# Transmitter.net
KiCad netlist of a schematic drawn in EAGLE
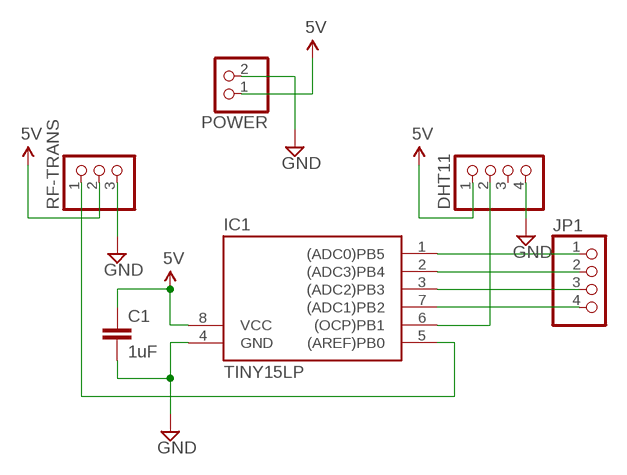
[diagram p0: schematic, sheet 1]

(export (version "E")
  (design (tool "Eeschema 10.0.6"))
  (components
    (comp (ref "C1")
      (value "1uF")
      (footprint "eagle-import:0805")
      (libsource (lib "eagle-import") (part "CAP0805"))
    )
    (comp (ref "DHT11")
      (value "PINHD-1X4")
      (footprint "eagle-import:1X04")
      (libsource (lib "eagle-import") (part "PINHD-1X4"))
    )
    (comp (ref "IC1")
      (value "TINY15LP")
      (footprint "eagle-import:DIL08")
      (libsource (lib "eagle-import") (part "TINY15LP"))
    )
    (comp (ref "JP1")
      (value "PINHD-1X4")
      (footprint "eagle-import:1X04")
      (libsource (lib "eagle-import") (part "PINHD-1X4"))
    )
    (comp (ref "POWER")
      (value "PINHD-1X2")
      (footprint "eagle-import:1X02")
      (libsource (lib "eagle-import") (part "PINHD-1X2"))
    )
    (comp (ref "RF-TRANS")
      (value "PINHD-1X3")
      (footprint "eagle-import:1X03")
      (libsource (lib "eagle-import") (part "PINHD-1X3"))
    )
  )
  (nets
    (net (code "1") (name "5V") (class "Default")
      (node (ref "C1") (pin "1") (pinfunction "1_1") (pintype "passive"))
      (node (ref "DHT11") (pin "1") (pinfunction "1_1") (pintype "passive"))
      (node (ref "IC1") (pin "8") (pinfunction "VCC_8") (pintype "power_in"))
      (node (ref "POWER") (pin "1") (pinfunction "1_1") (pintype "passive"))
      (node (ref "RF-TRANS") (pin "2") (pinfunction "2_2") (pintype "passive"))
    )
    (net (code "2") (name "GND") (class "Default")
      (node (ref "C1") (pin "2") (pinfunction "2_2") (pintype "passive"))
      (node (ref "DHT11") (pin "4") (pinfunction "4_4") (pintype "passive"))
      (node (ref "IC1") (pin "4") (pinfunction "GND_4") (pintype "power_in"))
      (node (ref "POWER") (pin "2") (pinfunction "2_2") (pintype "passive"))
      (node (ref "RF-TRANS") (pin "3") (pinfunction "3_3") (pintype "passive"))
    )
    (net (code "3") (name "Net-(IC1-(ADC0)PB5)") (class "Default")
      (node (ref "IC1") (pin "1") (pinfunction "(ADC0)PB5_1") (pintype "bidirectional"))
      (node (ref "JP1") (pin "1") (pinfunction "1_1") (pintype "passive"))
    )
    (net (code "4") (name "Net-(IC1-(ADC1)PB2)") (class "Default")
      (node (ref "IC1") (pin "7") (pinfunction "(ADC1)PB2_7") (pintype "bidirectional"))
      (node (ref "JP1") (pin "4") (pinfunction "4_4") (pintype "passive"))
    )
    (net (code "5") (name "Net-(IC1-(ADC2)PB3)") (class "Default")
      (node (ref "IC1") (pin "3") (pinfunction "(ADC2)PB3_3") (pintype "bidirectional"))
      (node (ref "JP1") (pin "3") (pinfunction "3_3") (pintype "passive"))
    )
    (net (code "6") (name "Net-(IC1-(ADC3)PB4)") (class "Default")
      (node (ref "IC1") (pin "2") (pinfunction "(ADC3)PB4_2") (pintype "bidirectional"))
      (node (ref "JP1") (pin "2") (pinfunction "2_2") (pintype "passive"))
    )
    (net (code "7") (name "Net-(IC1-(AREF)PB0)") (class "Default")
      (node (ref "IC1") (pin "5") (pinfunction "(AREF)PB0_5") (pintype "bidirectional"))
      (node (ref "RF-TRANS") (pin "1") (pinfunction "1_1") (pintype "passive"))
    )
    (net (code "8") (name "Net-(IC1-(OCP)PB1)") (class "Default")
      (node (ref "DHT11") (pin "2") (pinfunction "2_2") (pintype "passive"))
      (node (ref "IC1") (pin "6") (pinfunction "(OCP)PB1_6") (pintype "bidirectional"))
    )
    (net (code "9") (name "unconnected-(DHT11-Pad3)") (class "Default")
      (node (ref "DHT11") (pin "3") (pinfunction "3_3") (pintype "passive"))
    )
  )
)
